# SH-C31A-V1_1.net
KiCad netlist of a schematic drawn in Altium Designer
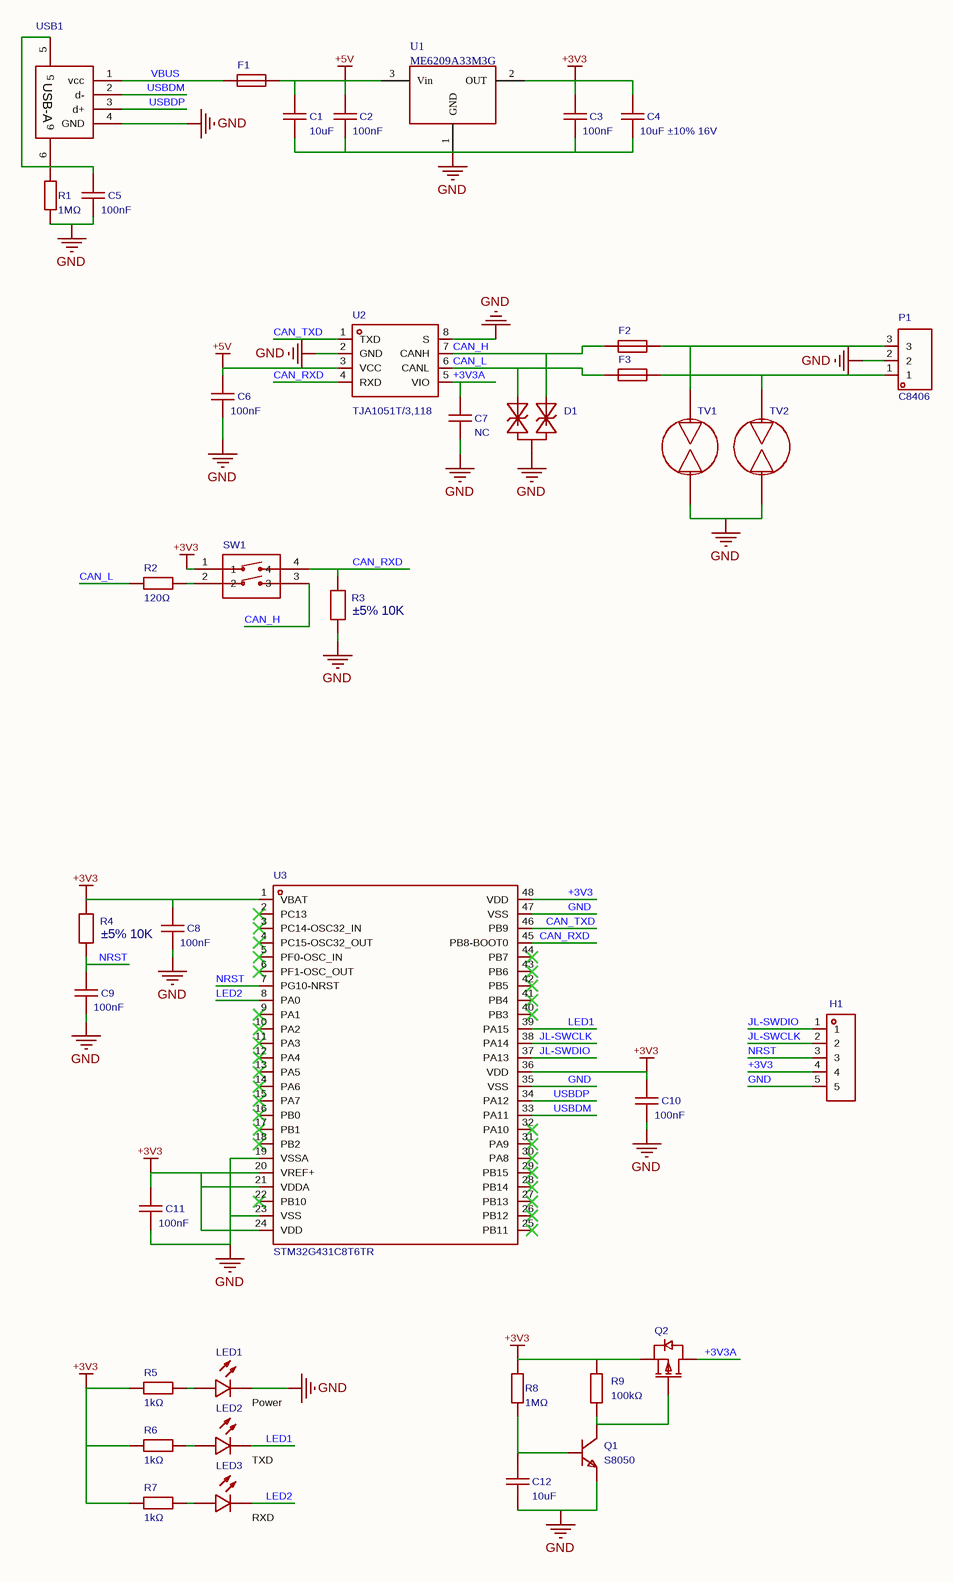
[diagram p0: SH-C31A-V1.1.SchDoc]

(export (version "E")
  (design (tool "Eeschema 10.0.6"))
  (components
    (comp (ref "C1")
      (value "10uF")
      (footprint "C0805_1")
      (description "Capacitance:10uF;Tolerance:±10%;Rated Voltage:16V;Dielectric (Temp. Coefficient):X5R;")
      (fields (field (name "MANUFACTURER") "SAMSUNG") (field (name "MANUFACTURERPART") "CL21A106KOQNNNE"))
      (libsource (lib "altium-import") (part "root_1_CL21A106KOQNNNE_"))
    )
    (comp (ref "C2")
      (value "100nF")
      (footprint "C0402_2")
      (description "Capacitance:100nF;Tolerance:±10%;Rated Voltage:25V;Dielectric (Temp. Coefficient):X7R;")
      (fields (field (name "MANUFACTURER") "FH") (field (name "MANUFACTURERPART") "0402B104K250NT"))
      (libsource (lib "altium-import") (part "root_1_0402B104K250NT_"))
    )
    (comp (ref "C3")
      (value "100nF")
      (footprint "C0402_2")
      (description "Capacitance:100nF;Tolerance:±10%;Rated Voltage:25V;Dielectric (Temp. Coefficient):X7R;")
      (fields (field (name "MANUFACTURER") "FH") (field (name "MANUFACTURERPART") "0402B104K250NT"))
      (libsource (lib "altium-import") (part "root_1_0402B104K250NT_"))
    )
    (comp (ref "C4")
      (value "10uF")
      (footprint "C0805_1")
      (description "Capacitance:10uF;Tolerance:±10%;Rated Voltage:16V;Dielectric (Temp. Coefficient):X5R;")
      (fields
        (field (name "LCSC PART NAME") "10uF ±10% 16V")
        (field (name "MANUFACTURER") "SAMSUNG")
        (field (name "MANUFACTURERPART") "CL21A106KOQNNNE")
      )
      (libsource (lib "altium-import") (part "root_1_CL21A106KOQNNNE_"))
    )
    (comp (ref "C5")
      (value "100nF")
      (footprint "C0402_2")
      (description "Capacitance:100nF;Tolerance:±10%;Rated Voltage:25V;Dielectric (Temp. Coefficient):X7R;")
      (fields (field (name "MANUFACTURER") "FH") (field (name "MANUFACTURERPART") "0402B104K250NT"))
      (libsource (lib "altium-import") (part "root_1_0402B104K250NT_"))
    )
    (comp (ref "C6")
      (value "100nF")
      (footprint "C0402_2")
      (description "Capacitance:100nF;Tolerance:±10%;Rated Voltage:25V;Dielectric (Temp. Coefficient):X7R;")
      (fields (field (name "MANUFACTURER") "FH") (field (name "MANUFACTURERPART") "0402B104K250NT"))
      (libsource (lib "altium-import") (part "root_1_0402B104K250NT_"))
    )
    (comp (ref "C7")
      (value "NC")
      (footprint "C0402_2")
      (description "Capacitance:100nF;Tolerance:±10%;Rated Voltage:25V;Dielectric (Temp. Coefficient):X7R;")
      (fields (field (name "MANUFACTURER") "FH") (field (name "MANUFACTURERPART") "0402B104K250NT"))
      (libsource (lib "altium-import") (part "root_1_0402B104K250NT_"))
    )
    (comp (ref "C8")
      (value "100nF")
      (footprint "C0402_2")
      (description "Capacitance:100nF;Tolerance:±10%;Rated Voltage:25V;Dielectric (Temp. Coefficient):X7R;")
      (fields (field (name "MANUFACTURER") "FH") (field (name "MANUFACTURERPART") "0402B104K250NT"))
      (libsource (lib "altium-import") (part "root_1_0402B104K250NT_"))
    )
    (comp (ref "C9")
      (value "100nF")
      (footprint "C0402_2")
      (description "Capacitance:100nF;Tolerance:±10%;Rated Voltage:25V;Dielectric (Temp. Coefficient):X7R;")
      (fields (field (name "MANUFACTURER") "FH") (field (name "MANUFACTURERPART") "0402B104K250NT"))
      (libsource (lib "altium-import") (part "root_1_0402B104K250NT_"))
    )
    (comp (ref "C10")
      (value "100nF")
      (footprint "C0402_2")
      (description "Capacitance:100nF;Tolerance:±10%;Rated Voltage:25V;Dielectric (Temp. Coefficient):X7R;")
      (fields (field (name "MANUFACTURER") "FH") (field (name "MANUFACTURERPART") "0402B104K250NT"))
      (libsource (lib "altium-import") (part "root_1_0402B104K250NT_"))
    )
    (comp (ref "C11")
      (value "100nF")
      (footprint "C0402_2")
      (description "Capacitance:100nF;Tolerance:±10%;Rated Voltage:25V;Dielectric (Temp. Coefficient):X7R;")
      (fields (field (name "MANUFACTURER") "FH") (field (name "MANUFACTURERPART") "0402B104K250NT"))
      (libsource (lib "altium-import") (part "root_1_0402B104K250NT_"))
    )
    (comp (ref "C12")
      (value "10uF")
      (footprint "C0603_1")
      (description "Capacitance:10uF;Tolerance:±10%;Rated Voltage:10V;Dielectric (Temp. Coefficient):X5R;")
      (fields (field (name "MANUFACTURER") "SAMSUNG") (field (name "MANUFACTURERPART") "CL10A106KP8NNNC"))
      (libsource (lib "altium-import") (part "root_1_CL10A106KP8NNNC_"))
    )
    (comp (ref "D1")
      (value "~")
      (footprint "SOT-23-3_L2.9-W1.3-P1.90-LS2.4-BR")
      (fields (field (name "MANUFACTURER") "TECH PUBLIC") (field (name "MANUFACTURERPART") "TPPESD12VL2BT"))
      (libsource (lib "altium-import") (part "root_2_TPPESD12VL2BT_"))
    )
    (comp (ref "F1")
      (value "~")
      (footprint "F0805")
      (description "Max Voltage:24V;Max Current:100A;Hold Current:100mA;Trip Current:300mA;")
      (fields (field (name "MANUFACTURER") "FUZETEC") (field (name "MANUFACTURERPART") "FSMD010-24-0805-R"))
      (libsource (lib "altium-import") (part "root_0_FSMD010-24-0805-R_"))
    )
    (comp (ref "F2")
      (value "SMD1206B020TF/24")
      (footprint "F1206_1")
      (description "Max Voltage:24V;Max Current:100A;Hold Current:200mA;Trip Current:420mA;Max Trip Time:100ms;")
      (fields (field (name "MANUFACTURER") "Brightking"))
      (libsource (lib "altium-import") (part "root_0_SMD1206B020TF/24_"))
    )
    (comp (ref "F3")
      (value "SMD1206B020TF/24")
      (footprint "F1206_1")
      (description "Max Voltage:24V;Max Current:100A;Hold Current:200mA;Trip Current:420mA;Max Trip Time:100ms;")
      (fields (field (name "MANUFACTURER") "Brightking"))
      (libsource (lib "altium-import") (part "root_0_SMD1206B020TF/24_"))
    )
    (comp (ref "H1")
      (value "~")
      (footprint "HDR-TH_5P-P2.54-V-M")
      (fields (field (name "MANUFACTURER") "XFCN") (field (name "MANUFACTURERPART") "PZ254V-11-05P"))
      (libsource (lib "altium-import") (part "root_0_PZ254V-11-05P_"))
    )
    (comp (ref "LED1")
      (value "~")
      (footprint "LED0603-RD_RED_1")
      (description "Emitted Color:Red;")
      (fields (field (name "MANUFACTURER") "NationStar") (field (name "MANUFACTURERPART") "NCD0603R1"))
      (libsource (lib "altium-import") (part "root_0_mirrored_NCD0603R1_C84263_"))
    )
    (comp (ref "LED2")
      (value "~")
      (footprint "LED0603-RD")
      (description "Emitted Color:Emerald Green;")
      (fields (field (name "MANUFACTURER") "NationStar") (field (name "MANUFACTURERPART") "NCD0603G1"))
      (libsource (lib "altium-import") (part "root_0_NCD0603G1_"))
    )
    (comp (ref "LED3")
      (value "~")
      (footprint "LED0603-RD")
      (description "Emitted Color:Emerald Green;")
      (fields (field (name "MANUFACTURER") "NationStar") (field (name "MANUFACTURERPART") "NCD0603G1"))
      (libsource (lib "altium-import") (part "root_0_NCD0603G1_"))
    )
    (comp (ref "P1")
      (value "WJ15EDGRC-3.81-3P")
      (footprint "CONN-TH_3P-P3.81_WJ15EDGRC-3.81-3P")
      (fields (field (name "SUPPLIER PART") "C8406") (field (name "MANUFACTURER") "KANGNEX"))
      (libsource (lib "altium-import") (part "root_2_mirrored_WJ15EDGRC-3.81-3P_"))
    )
    (comp (ref "Q1")
      (value "S8050")
      (footprint "SOT-23_L2.9-W1.3-P1.90-LS2.4-BR")
      (fields (field (name "MANUFACTURER PART") "S8050") (field (name "MANUFACTURER") "Slkor"))
      (libsource (lib "altium-import") (part "root_0_S8050_C444723_"))
    )
    (comp (ref "Q2")
      (value "SI2301")
      (footprint "SOT-23-3_L2.9-W1.3-P1.90-LS2.4-BR_2")
      (fields (field (name "MANUFACTURER") "YONGYUTAI"))
      (libsource (lib "altium-import") (part "root_1_mirrored_SI2301_C2891731_"))
    )
    (comp (ref "R1")
      (value "1MΩ")
      (footprint "R0603")
      (fields
        (field (name "MANUFACTURER") "UNI-ROYAL")
        (field (name "MANUFACTURERPART") "0603WAJ0105T5E")
        (field (name "TOLERANCE") "±5%")
      )
      (libsource (lib "altium-import") (part "root_1_0603WAJ0105T5E_"))
    )
    (comp (ref "R2")
      (value "120Ω")
      (footprint "R0805")
      (fields
        (field (name "MANUFACTURER") "UNI-ROYAL")
        (field (name "MANUFACTURERPART") "TC0525F1200T5E")
        (field (name "TOLERANCE") "±1%")
      )
      (libsource (lib "altium-import") (part "root_0_TC0525F1200T5E_"))
    )
    (comp (ref "R3")
      (value "~")
      (footprint "R0402")
      (fields
        (field (name "MANUFACTURER PART") "SCR0402J10K")
        (field (name "LCSC PART NAME") "±5% 10K")
        (field (name "MANUFACTURER") "VO")
      )
      (libsource (lib "altium-import") (part "root_1_SCR0402J10K_"))
    )
    (comp (ref "R4")
      (value "~")
      (footprint "R0402")
      (fields
        (field (name "LCSC PART NAME") "±5% 10K")
        (field (name "MANUFACTURER") "VO")
        (field (name "MANUFACTURERPART") "SCR0402J10K")
      )
      (libsource (lib "altium-import") (part "root_1_SCR0402J10K_"))
    )
    (comp (ref "R5")
      (value "1kΩ")
      (footprint "R0402")
      (fields
        (field (name "MANUFACTURER") "YAGEO")
        (field (name "MANUFACTURERPART") "RC0402JR-071KL")
        (field (name "TOLERANCE") "±5%")
      )
      (libsource (lib "altium-import") (part "root_0_RC0402JR-071KL_"))
    )
    (comp (ref "R6")
      (value "1kΩ")
      (footprint "R0402")
      (fields
        (field (name "MANUFACTURER") "YAGEO")
        (field (name "MANUFACTURERPART") "RC0402JR-071KL")
        (field (name "TOLERANCE") "±5%")
      )
      (libsource (lib "altium-import") (part "root_0_RC0402JR-071KL_"))
    )
    (comp (ref "R7")
      (value "1kΩ")
      (footprint "R0402")
      (fields
        (field (name "MANUFACTURER") "YAGEO")
        (field (name "MANUFACTURERPART") "RC0402JR-071KL")
        (field (name "TOLERANCE") "±5%")
      )
      (libsource (lib "altium-import") (part "root_0_RC0402JR-071KL_"))
    )
    (comp (ref "R8")
      (value "1MΩ")
      (footprint "R0603")
      (fields
        (field (name "MANUFACTURER") "UNI-ROYAL")
        (field (name "MANUFACTURERPART") "0603WAJ0105T5E")
        (field (name "TOLERANCE") "±5%")
      )
      (libsource (lib "altium-import") (part "root_1_0603WAJ0105T5E_"))
    )
    (comp (ref "R9")
      (value "100kΩ")
      (footprint "R0603")
      (description "Resistor Type:Thick Film Resistor;Resistance:100kΩ;Tolerance:±5%;Power:100mW;")
      (fields (field (name "MANUFACTURER") "UNI-ROYAL") (field (name "MANUFACTURERPART") "0603WAJ0104T5E"))
      (libsource (lib "altium-import") (part "root_1_0603WAJ0104T5E_"))
    )
    (comp (ref "SW1")
      (value "~")
      (footprint "SW-SMD_4P-L6.5-W6.0-P2.54-LS9.8")
      (description "SMD DIP switch, 2.54mm pitch, 2 positions, side-actuated long lever")
      (fields (field (name "MANUFACTURERPART") "NPM-02-V-T/R"))
      (libsource (lib "altium-import") (part "root_0_NPM-02-V-T/R_"))
    )
    (comp (ref "TV1")
      (value "~")
      (footprint "DIO-DT-SMD_L4.5-W3.2")
      (fields
        (field (name "MANUFACTURER") "RUILON")
        (field (name "MANUFACTURERPART") "SMD4532-090NF")
        (field (name "TOLERANCE") "±30%")
      )
      (libsource (lib "altium-import") (part "root_0_SMD4532-090NF_"))
    )
    (comp (ref "TV2")
      (value "~")
      (footprint "DIO-DT-SMD_L4.5-W3.2")
      (fields
        (field (name "MANUFACTURER") "RUILON")
        (field (name "MANUFACTURERPART") "SMD4532-090NF")
        (field (name "TOLERANCE") "±30%")
      )
      (libsource (lib "altium-import") (part "root_0_SMD4532-090NF_"))
    )
    (comp (ref "U1")
      (value "ME6209A33M3G")
      (footprint "SOT-23(SOT-23-3)")
      (libsource (lib "altium-import") (part "root_0_ME6209A33M3G_"))
    )
    (comp (ref "U2")
      (value "TJA1051T/3,118")
      (footprint "SOIC-8_L4.9-W3.9-P1.27-LS6.0-BL")
      (description "Type:-;")
      (fields (field (name "MANUFACTURER PART") "TJA1051T/3,118") (field (name "MANUFACTURER") "NXP"))
      (libsource (lib "altium-import") (part "root_0_TJA1051T/3,118_"))
    )
    (comp (ref "U3")
      (value "STM32G431C8T6TR")
      (footprint "LQFP-48_L7.0-W7.0-P0.50-LS9.0-BL_1")
      (fields (field (name "MANUFACTURER PART") "STM32G431C8T6TR") (field (name "MANUFACTURER") "ST"))
      (libsource (lib "altium-import") (part "root_0_STM32G431C8T6TR_"))
    )
    (comp (ref "USB1")
      (value "~")
      (footprint "USB-A-SMD_U-G-04WS-W-01")
      (description "Connector Type:Type-A;Standard:USB 2.0;Gender:Male;Contacts:4;Ports:1;")
      (fields (field (name "MANUFACTURER") "HRO") (field (name "MANUFACTURERPART") "U-G-04WS-W-01"))
      (libsource (lib "altium-import") (part "root_0_U-G-04WS-W-01_"))
    )
  )
  (nets
    (net (code "1") (name "+3V3") (class "Default")
      (node (ref "C10") (pin "2") (pinfunction "2_2") (pintype "passive"))
      (node (ref "C11") (pin "2") (pinfunction "2_2") (pintype "passive"))
      (node (ref "C3") (pin "2") (pinfunction "2_2") (pintype "passive"))
      (node (ref "C4") (pin "2") (pinfunction "2_2") (pintype "passive"))
      (node (ref "C8") (pin "2") (pinfunction "2_2") (pintype "passive"))
      (node (ref "H1") (pin "4") (pinfunction "4_4") (pintype "passive"))
      (node (ref "Q2") (pin "2") (pinfunction "S_2") (pintype "passive"))
      (node (ref "R4") (pin "2") (pinfunction "2_2") (pintype "passive"))
      (node (ref "R5") (pin "1") (pinfunction "1_1") (pintype "passive"))
      (node (ref "R6") (pin "1") (pinfunction "1_1") (pintype "passive"))
      (node (ref "R7") (pin "1") (pinfunction "1_1") (pintype "passive"))
      (node (ref "R8") (pin "2") (pinfunction "2_2") (pintype "passive"))
      (node (ref "R9") (pin "2") (pinfunction "2_2") (pintype "passive"))
      (node (ref "SW1") (pin "1") (pinfunction "1_1") (pintype "passive"))
      (node (ref "U1") (pin "2") (pinfunction "OUT_2") (pintype "passive"))
      (node (ref "U3") (pin "1") (pinfunction "VBAT_1") (pintype "passive"))
      (node (ref "U3") (pin "20") (pinfunction "VREF+_20") (pintype "passive"))
      (node (ref "U3") (pin "21") (pinfunction "VDDA_21") (pintype "passive"))
      (node (ref "U3") (pin "24") (pinfunction "VDD_24") (pintype "passive"))
      (node (ref "U3") (pin "36") (pinfunction "VDD_36") (pintype "passive"))
      (node (ref "U3") (pin "48") (pinfunction "VDD_48") (pintype "passive"))
    )
    (net (code "2") (name "+5V") (class "Default")
      (node (ref "C1") (pin "2") (pinfunction "2_2") (pintype "passive"))
      (node (ref "C2") (pin "2") (pinfunction "2_2") (pintype "passive"))
      (node (ref "C6") (pin "2") (pinfunction "2_2") (pintype "passive"))
      (node (ref "F1") (pin "2") (pinfunction "2_2") (pintype "passive"))
      (node (ref "U1") (pin "3") (pinfunction "Vin_3") (pintype "passive"))
      (node (ref "U2") (pin "3") (pinfunction "VCC_3") (pintype "passive"))
    )
    (net (code "3") (name "/+3V3A") (class "Default")
      (node (ref "C7") (pin "2") (pinfunction "2_2") (pintype "passive"))
      (node (ref "Q2") (pin "3") (pinfunction "D_3") (pintype "passive"))
      (node (ref "U2") (pin "5") (pinfunction "VIO_5") (pintype "passive"))
    )
    (net (code "4") (name "/CAN_H") (class "Default")
      (node (ref "D1") (pin "1") (pinfunction "1_1") (pintype "passive"))
      (node (ref "F2") (pin "1") (pinfunction "1_1") (pintype "passive"))
      (node (ref "SW1") (pin "3") (pinfunction "3_3") (pintype "passive"))
      (node (ref "U2") (pin "7") (pinfunction "CANH_7") (pintype "passive"))
    )
    (net (code "5") (name "/CAN_L") (class "Default")
      (node (ref "D1") (pin "2") (pinfunction "2_2") (pintype "passive"))
      (node (ref "F3") (pin "1") (pinfunction "1_1") (pintype "passive"))
      (node (ref "R2") (pin "1") (pinfunction "1_1") (pintype "passive"))
      (node (ref "U2") (pin "6") (pinfunction "CANL_6") (pintype "passive"))
    )
    (net (code "6") (name "/CAN_RXD") (class "Default")
      (node (ref "R3") (pin "2") (pinfunction "2_2") (pintype "passive"))
      (node (ref "SW1") (pin "4") (pinfunction "4_4") (pintype "passive"))
      (node (ref "U2") (pin "4") (pinfunction "RXD_4") (pintype "passive"))
      (node (ref "U3") (pin "45") (pinfunction "PB8-BOOT0_45") (pintype "passive"))
    )
    (net (code "7") (name "/CAN_TXD") (class "Default")
      (node (ref "U2") (pin "1") (pinfunction "TXD_1") (pintype "passive"))
      (node (ref "U3") (pin "46") (pinfunction "PB9_46") (pintype "passive"))
    )
    (net (code "8") (name "/JL-SWCLK") (class "Default")
      (node (ref "H1") (pin "2") (pinfunction "2_2") (pintype "passive"))
      (node (ref "U3") (pin "38") (pinfunction "PA14_38") (pintype "passive"))
    )
    (net (code "9") (name "/JL-SWDIO") (class "Default")
      (node (ref "H1") (pin "1") (pinfunction "1_1") (pintype "passive"))
      (node (ref "U3") (pin "37") (pinfunction "PA13_37") (pintype "passive"))
    )
    (net (code "10") (name "/LED1") (class "Default")
      (node (ref "LED2") (pin "1") (pinfunction "K_1") (pintype "passive"))
      (node (ref "U3") (pin "39") (pinfunction "PA15_39") (pintype "passive"))
    )
    (net (code "11") (name "/LED2") (class "Default")
      (node (ref "LED3") (pin "1") (pinfunction "K_1") (pintype "passive"))
      (node (ref "U3") (pin "8") (pinfunction "PA0_8") (pintype "passive"))
    )
    (net (code "12") (name "/NRST") (class "Default")
      (node (ref "C9") (pin "2") (pinfunction "2_2") (pintype "passive"))
      (node (ref "H1") (pin "3") (pinfunction "3_3") (pintype "passive"))
      (node (ref "R4") (pin "1") (pinfunction "1_1") (pintype "passive"))
      (node (ref "U3") (pin "7") (pinfunction "PG10-NRST_7") (pintype "passive"))
    )
    (net (code "13") (name "/USBDM") (class "Default")
      (node (ref "U3") (pin "33") (pinfunction "PA11_33") (pintype "passive"))
      (node (ref "USB1") (pin "2") (pinfunction "d-_2") (pintype "passive"))
    )
    (net (code "14") (name "/USBDP") (class "Default")
      (node (ref "U3") (pin "34") (pinfunction "PA12_34") (pintype "passive"))
      (node (ref "USB1") (pin "3") (pinfunction "d+_3") (pintype "passive"))
    )
    (net (code "15") (name "/VBUS") (class "Default")
      (node (ref "F1") (pin "1") (pinfunction "1_1") (pintype "passive"))
      (node (ref "USB1") (pin "1") (pinfunction "vcc_1") (pintype "passive"))
    )
    (net (code "16") (name "GND") (class "Default")
      (node (ref "C1") (pin "1") (pinfunction "1_1") (pintype "passive"))
      (node (ref "C10") (pin "1") (pinfunction "1_1") (pintype "passive"))
      (node (ref "C11") (pin "1") (pinfunction "1_1") (pintype "passive"))
      (node (ref "C12") (pin "1") (pinfunction "1_1") (pintype "passive"))
      (node (ref "C2") (pin "1") (pinfunction "1_1") (pintype "passive"))
      (node (ref "C3") (pin "1") (pinfunction "1_1") (pintype "passive"))
      (node (ref "C4") (pin "1") (pinfunction "1_1") (pintype "passive"))
      (node (ref "C5") (pin "1") (pinfunction "1_1") (pintype "passive"))
      (node (ref "C6") (pin "1") (pinfunction "1_1") (pintype "passive"))
      (node (ref "C7") (pin "1") (pinfunction "1_1") (pintype "passive"))
      (node (ref "C8") (pin "1") (pinfunction "1_1") (pintype "passive"))
      (node (ref "C9") (pin "1") (pinfunction "1_1") (pintype "passive"))
      (node (ref "D1") (pin "3") (pinfunction "3_3") (pintype "passive"))
      (node (ref "H1") (pin "5") (pinfunction "5_5") (pintype "passive"))
      (node (ref "LED1") (pin "1") (pinfunction "K_1") (pintype "passive"))
      (node (ref "P1") (pin "2") (pinfunction "2_2") (pintype "passive"))
      (node (ref "Q1") (pin "2") (pinfunction "E_2") (pintype "passive"))
      (node (ref "R1") (pin "1") (pinfunction "1_1") (pintype "passive"))
      (node (ref "R3") (pin "1") (pinfunction "1_1") (pintype "passive"))
      (node (ref "TV1") (pin "2") (pinfunction "2_2") (pintype "passive"))
      (node (ref "TV2") (pin "2") (pinfunction "2_2") (pintype "passive"))
      (node (ref "U1") (pin "1") (pinfunction "GND_1") (pintype "passive"))
      (node (ref "U2") (pin "2") (pinfunction "GND_2") (pintype "passive"))
      (node (ref "U2") (pin "8") (pinfunction "S_8") (pintype "passive"))
      (node (ref "U3") (pin "19") (pinfunction "VSSA_19") (pintype "passive"))
      (node (ref "U3") (pin "23") (pinfunction "VSS_23") (pintype "passive"))
      (node (ref "U3") (pin "35") (pinfunction "VSS_35") (pintype "passive"))
      (node (ref "U3") (pin "47") (pinfunction "VSS_47") (pintype "passive"))
      (node (ref "USB1") (pin "4") (pinfunction "GND_4") (pintype "passive"))
    )
    (net (code "17") (name "Net-(C5-Pad2)") (class "Default")
      (node (ref "C5") (pin "2") (pinfunction "2_2") (pintype "passive"))
      (node (ref "R1") (pin "2") (pinfunction "2_2") (pintype "passive"))
      (node (ref "USB1") (pin "5") (pinfunction "5_5") (pintype "passive"))
      (node (ref "USB1") (pin "6") (pinfunction "6_6") (pintype "passive"))
    )
    (net (code "18") (name "Net-(F2-Pad2)") (class "Default")
      (node (ref "F2") (pin "2") (pinfunction "2_2") (pintype "passive"))
      (node (ref "P1") (pin "3") (pinfunction "3_3") (pintype "passive"))
      (node (ref "TV1") (pin "1") (pinfunction "1_1") (pintype "passive"))
    )
    (net (code "19") (name "Net-(F3-Pad2)") (class "Default")
      (node (ref "F3") (pin "2") (pinfunction "2_2") (pintype "passive"))
      (node (ref "P1") (pin "1") (pinfunction "1_1") (pintype "passive"))
      (node (ref "TV2") (pin "1") (pinfunction "1_1") (pintype "passive"))
    )
    (net (code "20") (name "Net-(LED1-A)") (class "Default")
      (node (ref "LED1") (pin "2") (pinfunction "A_2") (pintype "passive"))
      (node (ref "R5") (pin "2") (pinfunction "2_2") (pintype "passive"))
    )
    (net (code "21") (name "Net-(LED2-A)") (class "Default")
      (node (ref "LED2") (pin "2") (pinfunction "A_2") (pintype "passive"))
      (node (ref "R6") (pin "2") (pinfunction "2_2") (pintype "passive"))
    )
    (net (code "22") (name "Net-(LED3-A)") (class "Default")
      (node (ref "LED3") (pin "2") (pinfunction "A_2") (pintype "passive"))
      (node (ref "R7") (pin "2") (pinfunction "2_2") (pintype "passive"))
    )
    (net (code "23") (name "Net-(Q1-B)") (class "Default")
      (node (ref "C12") (pin "2") (pinfunction "2_2") (pintype "passive"))
      (node (ref "Q1") (pin "1") (pinfunction "B_1") (pintype "passive"))
      (node (ref "R8") (pin "1") (pinfunction "1_1") (pintype "passive"))
    )
    (net (code "24") (name "Net-(Q1-C)") (class "Default")
      (node (ref "Q1") (pin "3") (pinfunction "C_3") (pintype "passive"))
      (node (ref "Q2") (pin "1") (pinfunction "G_1") (pintype "passive"))
      (node (ref "R9") (pin "1") (pinfunction "1_1") (pintype "passive"))
    )
    (net (code "25") (name "Net-(R2-Pad2)") (class "Default")
      (node (ref "R2") (pin "2") (pinfunction "2_2") (pintype "passive"))
      (node (ref "SW1") (pin "2") (pinfunction "2_2") (pintype "passive"))
    )
    (net (code "26") (name "unconnected-(U3-PA1-Pad9)") (class "Default")
      (node (ref "U3") (pin "9") (pinfunction "PA1_9") (pintype "passive+no_connect"))
    )
    (net (code "27") (name "unconnected-(U3-PA2-Pad10)") (class "Default")
      (node (ref "U3") (pin "10") (pinfunction "PA2_10") (pintype "passive+no_connect"))
    )
    (net (code "28") (name "unconnected-(U3-PA3-Pad11)") (class "Default")
      (node (ref "U3") (pin "11") (pinfunction "PA3_11") (pintype "passive+no_connect"))
    )
    (net (code "29") (name "unconnected-(U3-PA4-Pad12)") (class "Default")
      (node (ref "U3") (pin "12") (pinfunction "PA4_12") (pintype "passive+no_connect"))
    )
    (net (code "30") (name "unconnected-(U3-PA5-Pad13)") (class "Default")
      (node (ref "U3") (pin "13") (pinfunction "PA5_13") (pintype "passive+no_connect"))
    )
    (net (code "31") (name "unconnected-(U3-PA6-Pad14)") (class "Default")
      (node (ref "U3") (pin "14") (pinfunction "PA6_14") (pintype "passive+no_connect"))
    )
    (net (code "32") (name "unconnected-(U3-PA7-Pad15)") (class "Default")
      (node (ref "U3") (pin "15") (pinfunction "PA7_15") (pintype "passive+no_connect"))
    )
    (net (code "33") (name "unconnected-(U3-PA8-Pad30)") (class "Default")
      (node (ref "U3") (pin "30") (pinfunction "PA8_30") (pintype "passive+no_connect"))
    )
    (net (code "34") (name "unconnected-(U3-PA9-Pad31)") (class "Default")
      (node (ref "U3") (pin "31") (pinfunction "PA9_31") (pintype "passive+no_connect"))
    )
    (net (code "35") (name "unconnected-(U3-PA10-Pad32)") (class "Default")
      (node (ref "U3") (pin "32") (pinfunction "PA10_32") (pintype "passive+no_connect"))
    )
    (net (code "36") (name "unconnected-(U3-PB0-Pad16)") (class "Default")
      (node (ref "U3") (pin "16") (pinfunction "PB0_16") (pintype "passive+no_connect"))
    )
    (net (code "37") (name "unconnected-(U3-PB1-Pad17)") (class "Default")
      (node (ref "U3") (pin "17") (pinfunction "PB1_17") (pintype "passive+no_connect"))
    )
    (net (code "38") (name "unconnected-(U3-PB2-Pad18)") (class "Default")
      (node (ref "U3") (pin "18") (pinfunction "PB2_18") (pintype "passive+no_connect"))
    )
    (net (code "39") (name "unconnected-(U3-PB3-Pad40)") (class "Default")
      (node (ref "U3") (pin "40") (pinfunction "PB3_40") (pintype "passive+no_connect"))
    )
    (net (code "40") (name "unconnected-(U3-PB4-Pad41)") (class "Default")
      (node (ref "U3") (pin "41") (pinfunction "PB4_41") (pintype "passive+no_connect"))
    )
    (net (code "41") (name "unconnected-(U3-PB5-Pad42)") (class "Default")
      (node (ref "U3") (pin "42") (pinfunction "PB5_42") (pintype "passive+no_connect"))
    )
    (net (code "42") (name "unconnected-(U3-PB6-Pad43)") (class "Default")
      (node (ref "U3") (pin "43") (pinfunction "PB6_43") (pintype "passive+no_connect"))
    )
    (net (code "43") (name "unconnected-(U3-PB7-Pad44)") (class "Default")
      (node (ref "U3") (pin "44") (pinfunction "PB7_44") (pintype "passive+no_connect"))
    )
    (net (code "44") (name "unconnected-(U3-PB10-Pad22)") (class "Default")
      (node (ref "U3") (pin "22") (pinfunction "PB10_22") (pintype "passive+no_connect"))
    )
    (net (code "45") (name "unconnected-(U3-PB11-Pad25)") (class "Default")
      (node (ref "U3") (pin "25") (pinfunction "PB11_25") (pintype "passive+no_connect"))
    )
    (net (code "46") (name "unconnected-(U3-PB12-Pad26)") (class "Default")
      (node (ref "U3") (pin "26") (pinfunction "PB12_26") (pintype "passive+no_connect"))
    )
    (net (code "47") (name "unconnected-(U3-PB13-Pad27)") (class "Default")
      (node (ref "U3") (pin "27") (pinfunction "PB13_27") (pintype "passive+no_connect"))
    )
    (net (code "48") (name "unconnected-(U3-PB14-Pad28)") (class "Default")
      (node (ref "U3") (pin "28") (pinfunction "PB14_28") (pintype "passive+no_connect"))
    )
    (net (code "49") (name "unconnected-(U3-PB15-Pad29)") (class "Default")
      (node (ref "U3") (pin "29") (pinfunction "PB15_29") (pintype "passive+no_connect"))
    )
    (net (code "50") (name "unconnected-(U3-PC13-Pad2)") (class "Default")
      (node (ref "U3") (pin "2") (pinfunction "PC13_2") (pintype "passive+no_connect"))
    )
    (net (code "51") (name "unconnected-(U3-PC14-OSC32_IN-Pad3)") (class "Default")
      (node (ref "U3") (pin "3") (pinfunction "PC14-OSC32_IN_3") (pintype "passive+no_connect"))
    )
    (net (code "52") (name "unconnected-(U3-PC15-OSC32_OUT-Pad4)") (class "Default")
      (node (ref "U3") (pin "4") (pinfunction "PC15-OSC32_OUT_4") (pintype "passive+no_connect"))
    )
    (net (code "53") (name "unconnected-(U3-PF0-OSC_IN-Pad5)") (class "Default")
      (node (ref "U3") (pin "5") (pinfunction "PF0-OSC_IN_5") (pintype "passive+no_connect"))
    )
    (net (code "54") (name "unconnected-(U3-PF1-OSC_OUT-Pad6)") (class "Default")
      (node (ref "U3") (pin "6") (pinfunction "PF1-OSC_OUT_6") (pintype "passive+no_connect"))
    )
  )
)
